# mechanical.net
KiCad netlist of a schematic drawn in Altium Designer
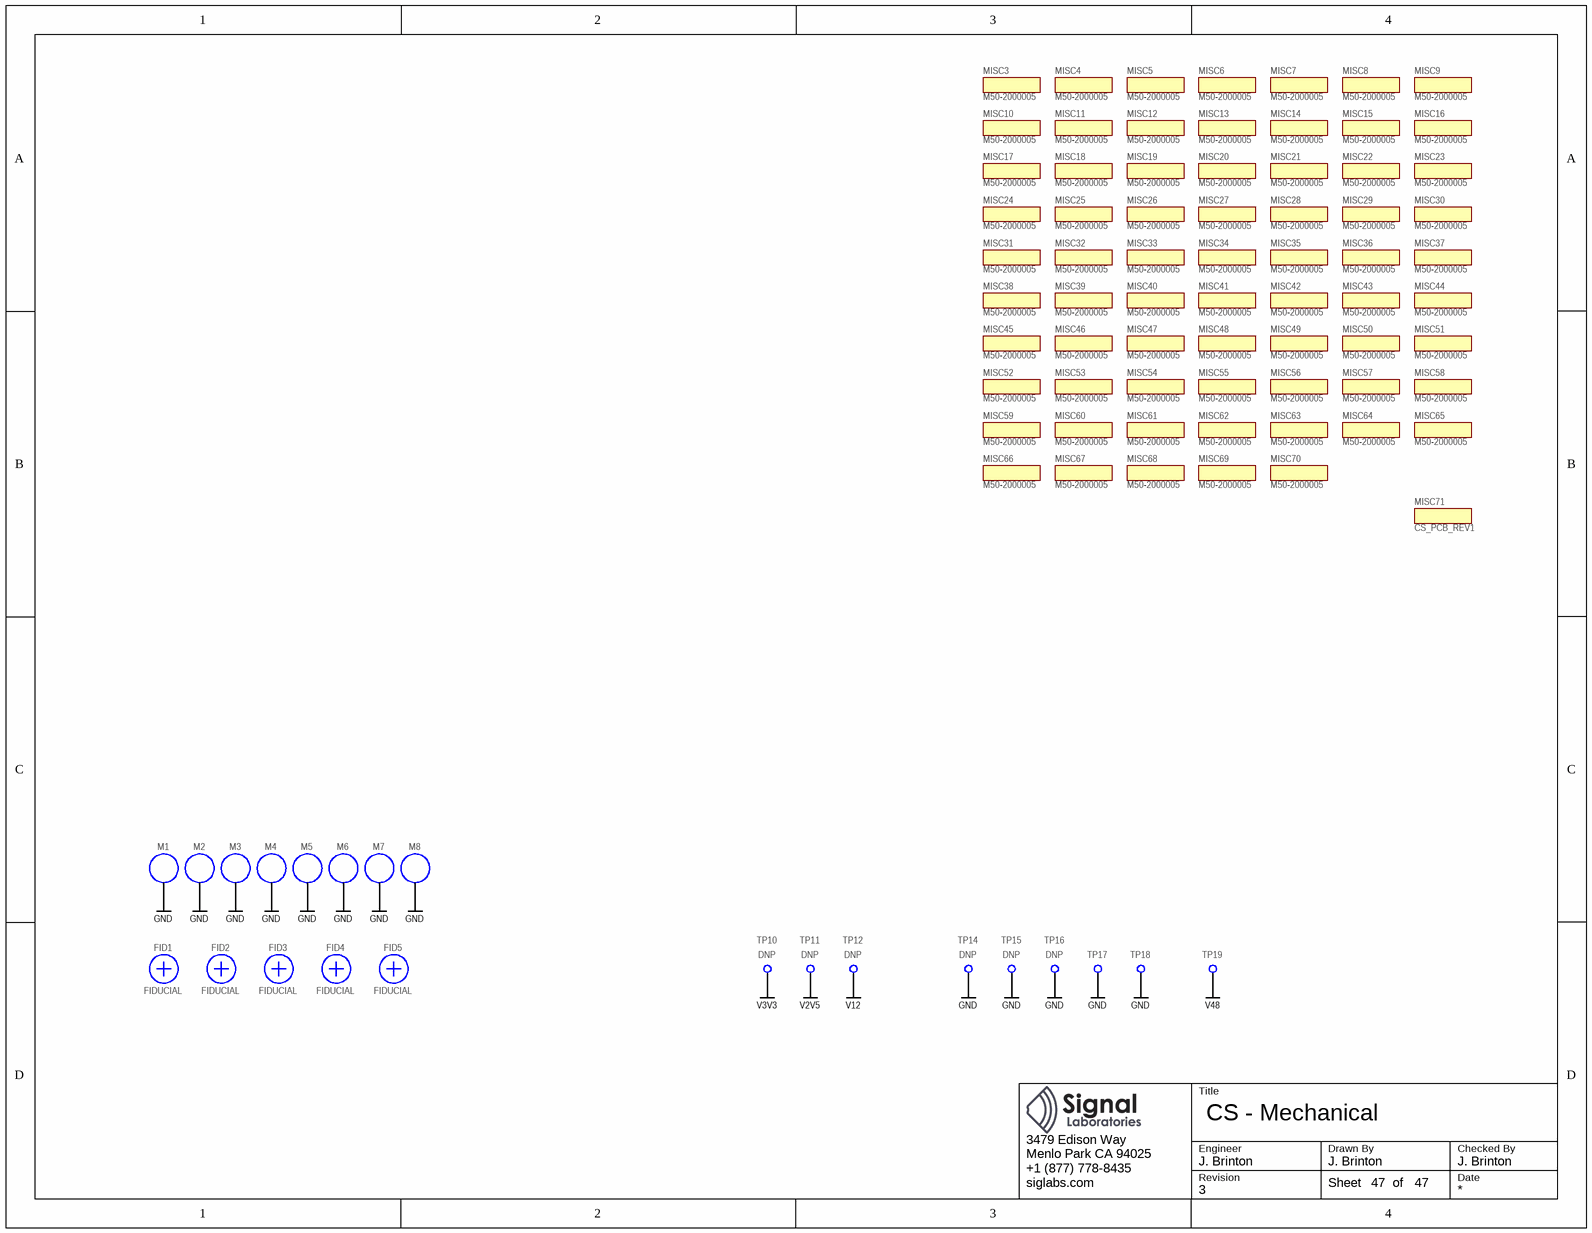
[diagram p0: mechanical.SchDoc]

(export (version "E")
  (design (tool "Eeschema 10.0.6"))
  (components
    (comp (ref "FID1")
      (value "FIDUCIAL")
      (footprint "FIDUCIAL")
      (libsource (lib "copper_suicide") (part "FIDUCIAL"))
    )
    (comp (ref "FID2")
      (value "FIDUCIAL")
      (footprint "FIDUCIAL")
      (libsource (lib "copper_suicide") (part "FIDUCIAL"))
    )
    (comp (ref "FID3")
      (value "FIDUCIAL")
      (footprint "FIDUCIAL")
      (libsource (lib "copper_suicide") (part "FIDUCIAL"))
    )
    (comp (ref "FID4")
      (value "FIDUCIAL")
      (footprint "FIDUCIAL")
      (libsource (lib "copper_suicide") (part "FIDUCIAL"))
    )
    (comp (ref "FID5")
      (value "FIDUCIAL")
      (footprint "FIDUCIAL")
      (libsource (lib "copper_suicide") (part "FIDUCIAL"))
    )
    (comp (ref "M1")
      (value "MOUNT")
      (footprint "MOUNTM3")
      (description "M3 Standard Fit Hole")
      (libsource (lib "copper_suicide") (part "MOUNT"))
    )
    (comp (ref "M2")
      (value "MOUNT")
      (footprint "MOUNTM3")
      (description "M3 Standard Fit Hole")
      (libsource (lib "copper_suicide") (part "MOUNT"))
    )
    (comp (ref "M3")
      (value "MOUNT")
      (footprint "MOUNTM3")
      (description "M3 Standard Fit Hole")
      (libsource (lib "copper_suicide") (part "MOUNT"))
    )
    (comp (ref "M4")
      (value "MOUNT")
      (footprint "MOUNTM3")
      (description "M3 Standard Fit Hole")
      (libsource (lib "copper_suicide") (part "MOUNT"))
    )
    (comp (ref "M5")
      (value "MOUNT")
      (footprint "MOUNTM3")
      (description "M3 Standard Fit Hole")
      (libsource (lib "copper_suicide") (part "MOUNT"))
    )
    (comp (ref "M6")
      (value "MOUNT")
      (footprint "MOUNTM3")
      (description "M3 Standard Fit Hole")
      (libsource (lib "copper_suicide") (part "MOUNT"))
    )
    (comp (ref "M7")
      (value "MOUNT")
      (footprint "MOUNTM3")
      (description "M3 Standard Fit Hole")
      (libsource (lib "copper_suicide") (part "MOUNT"))
    )
    (comp (ref "M8")
      (value "MOUNT")
      (footprint "MOUNTM3")
      (description "M3 Standard Fit Hole")
      (libsource (lib "copper_suicide") (part "MOUNT"))
    )
    (comp (ref "MISC3")
      (value "M50-2000005")
      (description "1.27mm Jumper Socket")
      (fields (field (name "MANUFACTURER") "Harwin"))
      (libsource (lib "harwin") (part "M50-1900005"))
    )
    (comp (ref "MISC4")
      (value "M50-2000005")
      (description "1.27mm Jumper Socket")
      (fields (field (name "MANUFACTURER") "Harwin"))
      (libsource (lib "harwin") (part "M50-1900005"))
    )
    (comp (ref "MISC5")
      (value "M50-2000005")
      (description "1.27mm Jumper Socket")
      (fields (field (name "MANUFACTURER") "Harwin"))
      (libsource (lib "harwin") (part "M50-1900005"))
    )
    (comp (ref "MISC6")
      (value "M50-2000005")
      (description "1.27mm Jumper Socket")
      (fields (field (name "MANUFACTURER") "Harwin"))
      (libsource (lib "harwin") (part "M50-1900005"))
    )
    (comp (ref "MISC7")
      (value "M50-2000005")
      (description "1.27mm Jumper Socket")
      (fields (field (name "MANUFACTURER") "Harwin"))
      (libsource (lib "harwin") (part "M50-1900005"))
    )
    (comp (ref "MISC8")
      (value "M50-2000005")
      (description "1.27mm Jumper Socket")
      (fields (field (name "MANUFACTURER") "Harwin"))
      (libsource (lib "harwin") (part "M50-1900005"))
    )
    (comp (ref "MISC9")
      (value "M50-2000005")
      (description "1.27mm Jumper Socket")
      (fields (field (name "MANUFACTURER") "Harwin"))
      (libsource (lib "harwin") (part "M50-1900005"))
    )
    (comp (ref "MISC10")
      (value "M50-2000005")
      (description "1.27mm Jumper Socket")
      (fields (field (name "MANUFACTURER") "Harwin"))
      (libsource (lib "harwin") (part "M50-1900005"))
    )
    (comp (ref "MISC11")
      (value "M50-2000005")
      (description "1.27mm Jumper Socket")
      (fields (field (name "MANUFACTURER") "Harwin"))
      (libsource (lib "harwin") (part "M50-1900005"))
    )
    (comp (ref "MISC12")
      (value "M50-2000005")
      (description "1.27mm Jumper Socket")
      (fields (field (name "MANUFACTURER") "Harwin"))
      (libsource (lib "harwin") (part "M50-1900005"))
    )
    (comp (ref "MISC13")
      (value "M50-2000005")
      (description "1.27mm Jumper Socket")
      (fields (field (name "MANUFACTURER") "Harwin"))
      (libsource (lib "harwin") (part "M50-1900005"))
    )
    (comp (ref "MISC14")
      (value "M50-2000005")
      (description "1.27mm Jumper Socket")
      (fields (field (name "MANUFACTURER") "Harwin"))
      (libsource (lib "harwin") (part "M50-1900005"))
    )
    (comp (ref "MISC15")
      (value "M50-2000005")
      (description "1.27mm Jumper Socket")
      (fields (field (name "MANUFACTURER") "Harwin"))
      (libsource (lib "harwin") (part "M50-1900005"))
    )
    (comp (ref "MISC16")
      (value "M50-2000005")
      (description "1.27mm Jumper Socket")
      (fields (field (name "MANUFACTURER") "Harwin"))
      (libsource (lib "harwin") (part "M50-1900005"))
    )
    (comp (ref "MISC17")
      (value "M50-2000005")
      (description "1.27mm Jumper Socket")
      (fields (field (name "MANUFACTURER") "Harwin"))
      (libsource (lib "harwin") (part "M50-1900005"))
    )
    (comp (ref "MISC18")
      (value "M50-2000005")
      (description "1.27mm Jumper Socket")
      (fields (field (name "MANUFACTURER") "Harwin"))
      (libsource (lib "harwin") (part "M50-1900005"))
    )
    (comp (ref "MISC19")
      (value "M50-2000005")
      (description "1.27mm Jumper Socket")
      (fields (field (name "MANUFACTURER") "Harwin"))
      (libsource (lib "harwin") (part "M50-1900005"))
    )
    (comp (ref "MISC20")
      (value "M50-2000005")
      (description "1.27mm Jumper Socket")
      (fields (field (name "MANUFACTURER") "Harwin"))
      (libsource (lib "harwin") (part "M50-1900005"))
    )
    (comp (ref "MISC21")
      (value "M50-2000005")
      (description "1.27mm Jumper Socket")
      (fields (field (name "MANUFACTURER") "Harwin"))
      (libsource (lib "harwin") (part "M50-1900005"))
    )
    (comp (ref "MISC22")
      (value "M50-2000005")
      (description "1.27mm Jumper Socket")
      (fields (field (name "MANUFACTURER") "Harwin"))
      (libsource (lib "harwin") (part "M50-1900005"))
    )
    (comp (ref "MISC23")
      (value "M50-2000005")
      (description "1.27mm Jumper Socket")
      (fields (field (name "MANUFACTURER") "Harwin"))
      (libsource (lib "harwin") (part "M50-1900005"))
    )
    (comp (ref "MISC24")
      (value "M50-2000005")
      (description "1.27mm Jumper Socket")
      (fields (field (name "MANUFACTURER") "Harwin"))
      (libsource (lib "harwin") (part "M50-1900005"))
    )
    (comp (ref "MISC25")
      (value "M50-2000005")
      (description "1.27mm Jumper Socket")
      (fields (field (name "MANUFACTURER") "Harwin"))
      (libsource (lib "harwin") (part "M50-1900005"))
    )
    (comp (ref "MISC26")
      (value "M50-2000005")
      (description "1.27mm Jumper Socket")
      (fields (field (name "MANUFACTURER") "Harwin"))
      (libsource (lib "harwin") (part "M50-1900005"))
    )
    (comp (ref "MISC27")
      (value "M50-2000005")
      (description "1.27mm Jumper Socket")
      (fields (field (name "MANUFACTURER") "Harwin"))
      (libsource (lib "harwin") (part "M50-1900005"))
    )
    (comp (ref "MISC28")
      (value "M50-2000005")
      (description "1.27mm Jumper Socket")
      (fields (field (name "MANUFACTURER") "Harwin"))
      (libsource (lib "harwin") (part "M50-1900005"))
    )
    (comp (ref "MISC29")
      (value "M50-2000005")
      (description "1.27mm Jumper Socket")
      (fields (field (name "MANUFACTURER") "Harwin"))
      (libsource (lib "harwin") (part "M50-1900005"))
    )
    (comp (ref "MISC30")
      (value "M50-2000005")
      (description "1.27mm Jumper Socket")
      (fields (field (name "MANUFACTURER") "Harwin"))
      (libsource (lib "harwin") (part "M50-1900005"))
    )
    (comp (ref "MISC31")
      (value "M50-2000005")
      (description "1.27mm Jumper Socket")
      (fields (field (name "MANUFACTURER") "Harwin"))
      (libsource (lib "harwin") (part "M50-1900005"))
    )
    (comp (ref "MISC32")
      (value "M50-2000005")
      (description "1.27mm Jumper Socket")
      (fields (field (name "MANUFACTURER") "Harwin"))
      (libsource (lib "harwin") (part "M50-1900005"))
    )
    (comp (ref "MISC33")
      (value "M50-2000005")
      (description "1.27mm Jumper Socket")
      (fields (field (name "MANUFACTURER") "Harwin"))
      (libsource (lib "harwin") (part "M50-1900005"))
    )
    (comp (ref "MISC34")
      (value "M50-2000005")
      (description "1.27mm Jumper Socket")
      (fields (field (name "MANUFACTURER") "Harwin"))
      (libsource (lib "harwin") (part "M50-1900005"))
    )
    (comp (ref "MISC35")
      (value "M50-2000005")
      (description "1.27mm Jumper Socket")
      (fields (field (name "MANUFACTURER") "Harwin"))
      (libsource (lib "harwin") (part "M50-1900005"))
    )
    (comp (ref "MISC36")
      (value "M50-2000005")
      (description "1.27mm Jumper Socket")
      (fields (field (name "MANUFACTURER") "Harwin"))
      (libsource (lib "harwin") (part "M50-1900005"))
    )
    (comp (ref "MISC37")
      (value "M50-2000005")
      (description "1.27mm Jumper Socket")
      (fields (field (name "MANUFACTURER") "Harwin"))
      (libsource (lib "harwin") (part "M50-1900005"))
    )
    (comp (ref "MISC38")
      (value "M50-2000005")
      (description "1.27mm Jumper Socket")
      (fields (field (name "MANUFACTURER") "Harwin"))
      (libsource (lib "harwin") (part "M50-1900005"))
    )
    (comp (ref "MISC39")
      (value "M50-2000005")
      (description "1.27mm Jumper Socket")
      (fields (field (name "MANUFACTURER") "Harwin"))
      (libsource (lib "harwin") (part "M50-1900005"))
    )
    (comp (ref "MISC40")
      (value "M50-2000005")
      (description "1.27mm Jumper Socket")
      (fields (field (name "MANUFACTURER") "Harwin"))
      (libsource (lib "harwin") (part "M50-1900005"))
    )
    (comp (ref "MISC41")
      (value "M50-2000005")
      (description "1.27mm Jumper Socket")
      (fields (field (name "MANUFACTURER") "Harwin"))
      (libsource (lib "harwin") (part "M50-1900005"))
    )
    (comp (ref "MISC42")
      (value "M50-2000005")
      (description "1.27mm Jumper Socket")
      (fields (field (name "MANUFACTURER") "Harwin"))
      (libsource (lib "harwin") (part "M50-1900005"))
    )
    (comp (ref "MISC43")
      (value "M50-2000005")
      (description "1.27mm Jumper Socket")
      (fields (field (name "MANUFACTURER") "Harwin"))
      (libsource (lib "harwin") (part "M50-1900005"))
    )
    (comp (ref "MISC44")
      (value "M50-2000005")
      (description "1.27mm Jumper Socket")
      (fields (field (name "MANUFACTURER") "Harwin"))
      (libsource (lib "harwin") (part "M50-1900005"))
    )
    (comp (ref "MISC45")
      (value "M50-2000005")
      (description "1.27mm Jumper Socket")
      (fields (field (name "MANUFACTURER") "Harwin"))
      (libsource (lib "harwin") (part "M50-1900005"))
    )
    (comp (ref "MISC46")
      (value "M50-2000005")
      (description "1.27mm Jumper Socket")
      (fields (field (name "MANUFACTURER") "Harwin"))
      (libsource (lib "harwin") (part "M50-1900005"))
    )
    (comp (ref "MISC47")
      (value "M50-2000005")
      (description "1.27mm Jumper Socket")
      (fields (field (name "MANUFACTURER") "Harwin"))
      (libsource (lib "harwin") (part "M50-1900005"))
    )
    (comp (ref "MISC48")
      (value "M50-2000005")
      (description "1.27mm Jumper Socket")
      (fields (field (name "MANUFACTURER") "Harwin"))
      (libsource (lib "harwin") (part "M50-1900005"))
    )
    (comp (ref "MISC49")
      (value "M50-2000005")
      (description "1.27mm Jumper Socket")
      (fields (field (name "MANUFACTURER") "Harwin"))
      (libsource (lib "harwin") (part "M50-1900005"))
    )
    (comp (ref "MISC50")
      (value "M50-2000005")
      (description "1.27mm Jumper Socket")
      (fields (field (name "MANUFACTURER") "Harwin"))
      (libsource (lib "harwin") (part "M50-1900005"))
    )
    (comp (ref "MISC51")
      (value "M50-2000005")
      (description "1.27mm Jumper Socket")
      (fields (field (name "MANUFACTURER") "Harwin"))
      (libsource (lib "harwin") (part "M50-1900005"))
    )
    (comp (ref "MISC52")
      (value "M50-2000005")
      (description "1.27mm Jumper Socket")
      (fields (field (name "MANUFACTURER") "Harwin"))
      (libsource (lib "harwin") (part "M50-1900005"))
    )
    (comp (ref "MISC53")
      (value "M50-2000005")
      (description "1.27mm Jumper Socket")
      (fields (field (name "MANUFACTURER") "Harwin"))
      (libsource (lib "harwin") (part "M50-1900005"))
    )
    (comp (ref "MISC54")
      (value "M50-2000005")
      (description "1.27mm Jumper Socket")
      (fields (field (name "MANUFACTURER") "Harwin"))
      (libsource (lib "harwin") (part "M50-1900005"))
    )
    (comp (ref "MISC55")
      (value "M50-2000005")
      (description "1.27mm Jumper Socket")
      (fields (field (name "MANUFACTURER") "Harwin"))
      (libsource (lib "harwin") (part "M50-1900005"))
    )
    (comp (ref "MISC56")
      (value "M50-2000005")
      (description "1.27mm Jumper Socket")
      (fields (field (name "MANUFACTURER") "Harwin"))
      (libsource (lib "harwin") (part "M50-1900005"))
    )
    (comp (ref "MISC57")
      (value "M50-2000005")
      (description "1.27mm Jumper Socket")
      (fields (field (name "MANUFACTURER") "Harwin"))
      (libsource (lib "harwin") (part "M50-1900005"))
    )
    (comp (ref "MISC58")
      (value "M50-2000005")
      (description "1.27mm Jumper Socket")
      (fields (field (name "MANUFACTURER") "Harwin"))
      (libsource (lib "harwin") (part "M50-1900005"))
    )
    (comp (ref "MISC59")
      (value "M50-2000005")
      (description "1.27mm Jumper Socket")
      (fields (field (name "MANUFACTURER") "Harwin"))
      (libsource (lib "harwin") (part "M50-1900005"))
    )
    (comp (ref "MISC60")
      (value "M50-2000005")
      (description "1.27mm Jumper Socket")
      (fields (field (name "MANUFACTURER") "Harwin"))
      (libsource (lib "harwin") (part "M50-1900005"))
    )
    (comp (ref "MISC61")
      (value "M50-2000005")
      (description "1.27mm Jumper Socket")
      (fields (field (name "MANUFACTURER") "Harwin"))
      (libsource (lib "harwin") (part "M50-1900005"))
    )
    (comp (ref "MISC62")
      (value "M50-2000005")
      (description "1.27mm Jumper Socket")
      (fields (field (name "MANUFACTURER") "Harwin"))
      (libsource (lib "harwin") (part "M50-1900005"))
    )
    (comp (ref "MISC63")
      (value "M50-2000005")
      (description "1.27mm Jumper Socket")
      (fields (field (name "MANUFACTURER") "Harwin"))
      (libsource (lib "harwin") (part "M50-1900005"))
    )
    (comp (ref "MISC64")
      (value "M50-2000005")
      (description "1.27mm Jumper Socket")
      (fields (field (name "MANUFACTURER") "Harwin"))
      (libsource (lib "harwin") (part "M50-1900005"))
    )
    (comp (ref "MISC65")
      (value "M50-2000005")
      (description "1.27mm Jumper Socket")
      (fields (field (name "MANUFACTURER") "Harwin"))
      (libsource (lib "harwin") (part "M50-1900005"))
    )
    (comp (ref "MISC66")
      (value "M50-2000005")
      (description "1.27mm Jumper Socket")
      (fields (field (name "MANUFACTURER") "Harwin"))
      (libsource (lib "harwin") (part "M50-1900005"))
    )
    (comp (ref "MISC67")
      (value "M50-2000005")
      (description "1.27mm Jumper Socket")
      (fields (field (name "MANUFACTURER") "Harwin"))
      (libsource (lib "harwin") (part "M50-1900005"))
    )
    (comp (ref "MISC68")
      (value "M50-2000005")
      (description "1.27mm Jumper Socket")
      (fields (field (name "MANUFACTURER") "Harwin"))
      (libsource (lib "harwin") (part "M50-1900005"))
    )
    (comp (ref "MISC69")
      (value "M50-2000005")
      (description "1.27mm Jumper Socket")
      (fields (field (name "MANUFACTURER") "Harwin"))
      (libsource (lib "harwin") (part "M50-1900005"))
    )
    (comp (ref "MISC70")
      (value "M50-2000005")
      (description "1.27mm Jumper Socket")
      (fields (field (name "MANUFACTURER") "Harwin"))
      (libsource (lib "harwin") (part "M50-1900005"))
    )
    (comp (ref "MISC71")
      (value "CS_PCB_REV1")
      (description "Copper Suicide PCB")
      (fields (field (name "MANUFACTURER") "Signal Laboratories, Inc."))
      (libsource (lib "harwin") (part "M50-1900005"))
    )
    (comp (ref "TP10")
      (value "5000")
      (footprint "TEST_POINT")
      (description "Thruhole Miniature Test Point")
      (fields (field (name "MANUFACTURER") "Keystone Electronics Corp") (field (name "DO NOT PLACE") "DNP"))
      (libsource (lib "generic") (part "TEST_POINT"))
    )
    (comp (ref "TP11")
      (value "5000")
      (footprint "TEST_POINT")
      (description "Thruhole Miniature Test Point")
      (fields (field (name "MANUFACTURER") "Keystone Electronics Corp") (field (name "DO NOT PLACE") "DNP"))
      (libsource (lib "generic") (part "TEST_POINT"))
    )
    (comp (ref "TP12")
      (value "5000")
      (footprint "TEST_POINT")
      (description "Thruhole Miniature Test Point")
      (fields (field (name "MANUFACTURER") "Keystone Electronics Corp") (field (name "DO NOT PLACE") "DNP"))
      (libsource (lib "generic") (part "TEST_POINT"))
    )
    (comp (ref "TP14")
      (value "5000")
      (footprint "TEST_POINT")
      (description "Thruhole Miniature Test Point")
      (fields (field (name "MANUFACTURER") "Keystone Electronics Corp") (field (name "DO NOT PLACE") "DNP"))
      (libsource (lib "generic") (part "TEST_POINT"))
    )
    (comp (ref "TP15")
      (value "5000")
      (footprint "TEST_POINT")
      (description "Thruhole Miniature Test Point")
      (fields (field (name "MANUFACTURER") "Keystone Electronics Corp") (field (name "DO NOT PLACE") "DNP"))
      (libsource (lib "generic") (part "TEST_POINT"))
    )
    (comp (ref "TP16")
      (value "5000")
      (footprint "TEST_POINT")
      (description "Thruhole Miniature Test Point")
      (fields (field (name "MANUFACTURER") "Keystone Electronics Corp") (field (name "DO NOT PLACE") "DNP"))
      (libsource (lib "generic") (part "TEST_POINT"))
    )
    (comp (ref "TP17")
      (value "5000")
      (footprint "TEST_POINT")
      (description "Thruhole Miniature Test Point")
      (fields (field (name "MANUFACTURER") "Keystone Electronics Corp"))
      (libsource (lib "generic") (part "TEST_POINT"))
    )
    (comp (ref "TP18")
      (value "5000")
      (footprint "TEST_POINT")
      (description "Thruhole Miniature Test Point")
      (fields (field (name "MANUFACTURER") "Keystone Electronics Corp"))
      (libsource (lib "generic") (part "TEST_POINT"))
    )
    (comp (ref "TP19")
      (value "5000")
      (footprint "TEST_POINT")
      (description "Thruhole Miniature Test Point")
      (fields (field (name "MANUFACTURER") "Keystone Electronics Corp"))
      (libsource (lib "generic") (part "TEST_POINT"))
    )
  )
  (nets
    (net (code "1") (name "GND") (class "Default")
      (node (ref "M1") (pin "1") (pinfunction "MNT_1") (pintype "passive"))
      (node (ref "M2") (pin "1") (pinfunction "MNT_1") (pintype "passive"))
      (node (ref "M3") (pin "1") (pinfunction "MNT_1") (pintype "passive"))
      (node (ref "M4") (pin "1") (pinfunction "MNT_1") (pintype "passive"))
      (node (ref "M5") (pin "1") (pinfunction "MNT_1") (pintype "passive"))
      (node (ref "M6") (pin "1") (pinfunction "MNT_1") (pintype "passive"))
      (node (ref "M7") (pin "1") (pinfunction "MNT_1") (pintype "passive"))
      (node (ref "M8") (pin "1") (pinfunction "MNT_1") (pintype "passive"))
      (node (ref "TP14") (pin "1") (pinfunction "1_1") (pintype "passive"))
      (node (ref "TP15") (pin "1") (pinfunction "1_1") (pintype "passive"))
      (node (ref "TP16") (pin "1") (pinfunction "1_1") (pintype "passive"))
      (node (ref "TP17") (pin "1") (pinfunction "1_1") (pintype "passive"))
      (node (ref "TP18") (pin "1") (pinfunction "1_1") (pintype "passive"))
    )
    (net (code "2") (name "V2V5") (class "Default")
      (node (ref "TP11") (pin "1") (pinfunction "1_1") (pintype "passive"))
    )
    (net (code "3") (name "V3V3") (class "Default")
      (node (ref "TP10") (pin "1") (pinfunction "1_1") (pintype "passive"))
    )
    (net (code "4") (name "V12") (class "Default")
      (node (ref "TP12") (pin "1") (pinfunction "1_1") (pintype "passive"))
    )
    (net (code "5") (name "V48") (class "Default")
      (node (ref "TP19") (pin "1") (pinfunction "1_1") (pintype "passive"))
    )
  )
)
